# RTC.net
KiCad netlist of a schematic drawn in Altium Designer
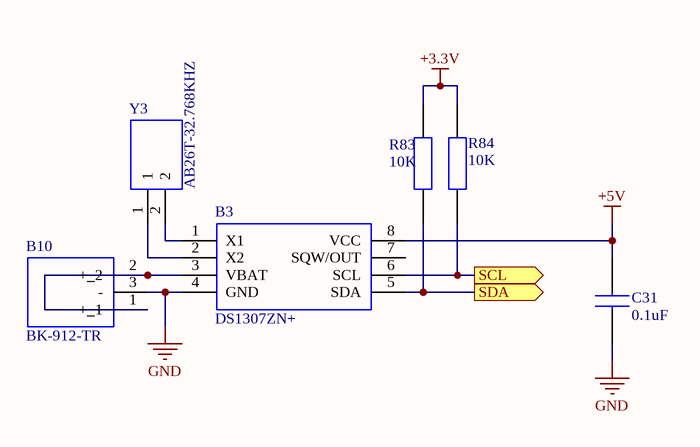
[diagram p0: RTC.SchDoc]

(export (version "E")
  (design (tool "Eeschema 10.0.6"))
  (components
    (comp (ref "B3")
      (value "DS1307ZN+")
      (footprint "SOIC127P600X175-8N")
      (description "DS1307ZN+, Real Time Clock, Calendar, Clock, 56B RAM, I2C, 8-Pin SOIC")
      (fields (field (name "MOUSER PART NUMBER") "700-DS1307ZN"))
      (libsource (lib "DS1307ZN+") (part "DS1307ZN+"))
    )
    (comp (ref "B10")
      (value "BK-912-TR")
      (footprint "BK912TR")
      (description "BATTERY RETAINER COIN 20MM SMD")
      (libsource (lib "Battery_Retainer") (part "BK-912-TR"))
    )
    (comp (ref "C31")
      (value "0.1uF")
      (footprint "CAPC1005X55N")
      (description "Multilayer Ceramic Capacitors MLCC - SMD/SMT 16V 0.1uF X7R 0402 20%")
      (fields
        (field (name "MANUFACTURER_PART_NUMBER") "C0402C104M4RECTU")
        (field (name "MOUSER PART NUMBER") "80-C0402C104M4RECTU")
      )
      (libsource (lib "0.1uF_0402") (part "C0402C104M4RECTU"))
    )
    (comp (ref "R83")
      (value "10K")
      (footprint "RESC1005X40N")
      (description "YAGEO (PHYCOMP) - RC0402JR-0710KL - RES, THICK FILM, 10K, 5%, 0.0625W, 0402")
      (fields
        (field (name "MANUFACTURER_PART_NUMBER") "RC0402JR-0710KL")
        (field (name "MOUSER PART NUMBER") "603-RC0402JR-0710KL")
      )
      (libsource (lib "10K_0402") (part "RC0402JR-0710KL"))
    )
    (comp (ref "R84")
      (value "10K")
      (footprint "RESC1005X40N")
      (description "YAGEO (PHYCOMP) - RC0402JR-0710KL - RES, THICK FILM, 10K, 5%, 0.0625W, 0402")
      (fields
        (field (name "MANUFACTURER_PART_NUMBER") "RC0402JR-0710KL")
        (field (name "MOUSER PART NUMBER") "603-RC0402JR-0710KL")
      )
      (libsource (lib "10K_0402") (part "RC0402JR-0710KL"))
    )
    (comp (ref "Y3")
      (value "AB26T-32.768KHZ")
      (footprint "AB26T")
      (description "Crystal 32.768kHz, +/-20ppm Cylindrical Can, Radial, 2.1 x 6.2mm")
      (fields (field (name "MOUSER PART NUMBER") "815-AB26T-32.768KHZ"))
      (libsource (lib "32.768KHZ_THT") (part "AB26T-32.768KHZ"))
    )
  )
  (nets
    (net (code "1") (name "+3.3V") (class "Default")
      (node (ref "R83") (pin "2") (pinfunction "2_2") (pintype "passive"))
      (node (ref "R84") (pin "2") (pinfunction "2_2") (pintype "passive"))
    )
    (net (code "2") (name "+5V") (class "Default")
      (node (ref "B3") (pin "8") (pinfunction "VCC_8") (pintype "power_in"))
      (node (ref "C31") (pin "2") (pinfunction "2_2") (pintype "passive"))
    )
    (net (code "3") (name "/SCL") (class "Default")
      (node (ref "B3") (pin "6") (pinfunction "SCL_6") (pintype "passive"))
      (node (ref "R84") (pin "1") (pinfunction "1_1") (pintype "passive"))
    )
    (net (code "4") (name "/SDA") (class "Default")
      (node (ref "B3") (pin "5") (pinfunction "SDA_5") (pintype "passive"))
      (node (ref "R83") (pin "1") (pinfunction "1_1") (pintype "passive"))
    )
    (net (code "5") (name "GND") (class "Default")
      (node (ref "B10") (pin "3") (pinfunction "-_3") (pintype "passive"))
      (node (ref "B3") (pin "4") (pinfunction "GND_4") (pintype "passive"))
      (node (ref "C31") (pin "1") (pinfunction "1_1") (pintype "passive"))
    )
    (net (code "6") (name "Net-(B3-X1)") (class "Default")
      (node (ref "B3") (pin "1") (pinfunction "X1_1") (pintype "passive"))
      (node (ref "Y3") (pin "2") (pinfunction "2_2") (pintype "passive"))
    )
    (net (code "7") (name "Net-(B3-X2)") (class "Default")
      (node (ref "B3") (pin "2") (pinfunction "X2_2") (pintype "passive"))
      (node (ref "Y3") (pin "1") (pinfunction "1_1") (pintype "passive"))
    )
    (net (code "8") (name "Net-(B10-+_1)") (class "Default")
      (node (ref "B10") (pin "1") (pinfunction "+_1_1") (pintype "passive"))
      (node (ref "B10") (pin "2") (pinfunction "+_2_2") (pintype "passive"))
      (node (ref "B3") (pin "3") (pinfunction "VBAT_3") (pintype "passive"))
    )
    (net (code "9") (name "unconnected-(B3-SQW{slash}OUT-Pad7)") (class "Default")
      (node (ref "B3") (pin "7") (pinfunction "SQW/OUT_7") (pintype "passive"))
    )
  )
)
